# NeoGeo-JAMMA-Supergun_PP.net
KiCad netlist of a schematic drawn in EAGLE
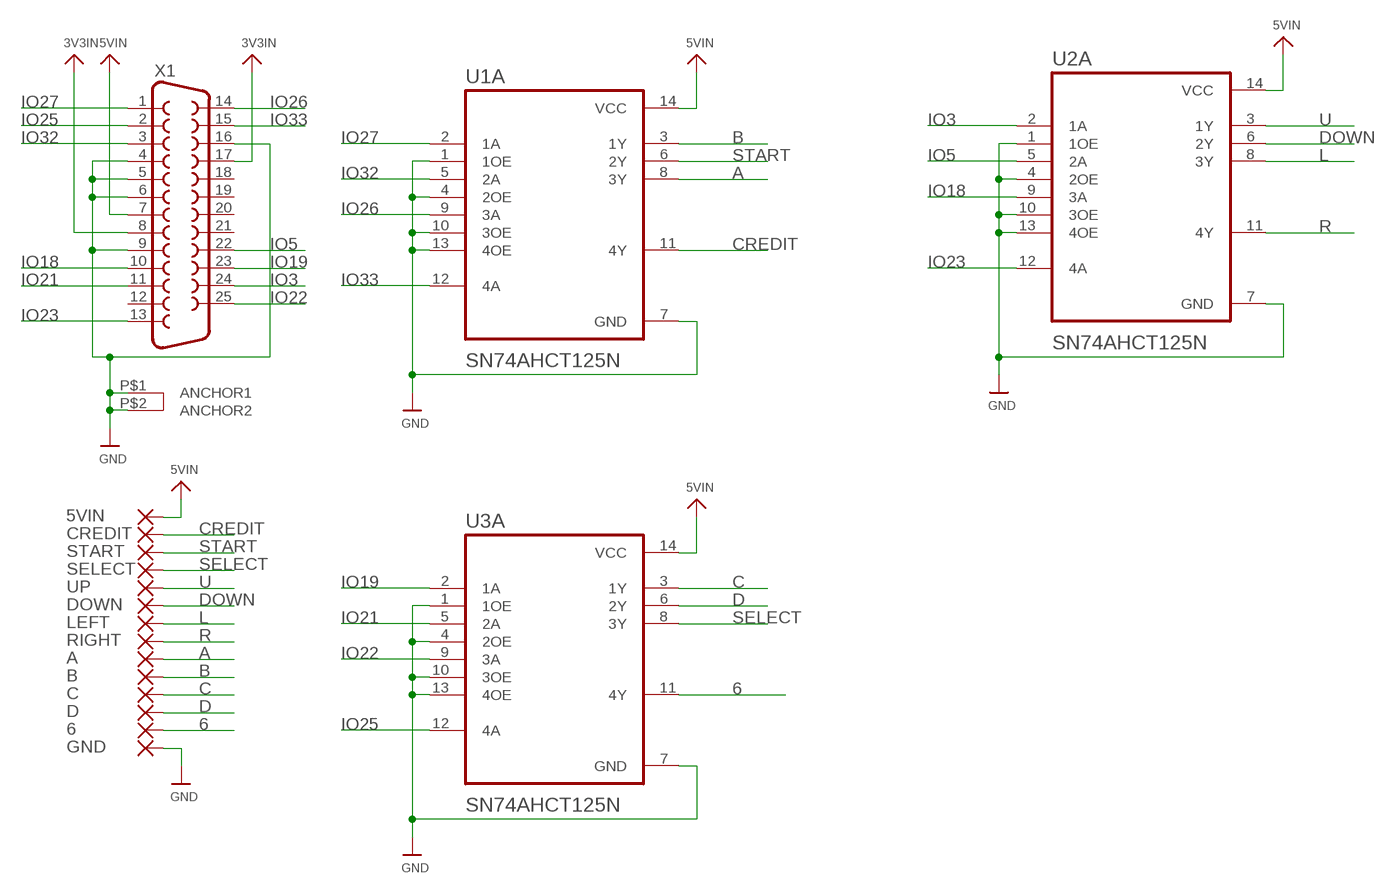
[diagram p0: schematic, sheet 1]

(export (version "E")
  (design (tool "Eeschema 10.0.6"))
  (components
    (comp (ref "5VIN")
      (value "SMD5")
      (footprint "eagle-import:SMD2,54-5,08")
      (libsource (lib "eagle-import") (part "SMD5"))
    )
    (comp (ref "6")
      (value "SMD5")
      (footprint "eagle-import:SMD2,54-5,08")
      (libsource (lib "eagle-import") (part "SMD5"))
    )
    (comp (ref "A")
      (value "SMD5")
      (footprint "eagle-import:SMD2,54-5,08")
      (libsource (lib "eagle-import") (part "SMD5"))
    )
    (comp (ref "B")
      (value "SMD5")
      (footprint "eagle-import:SMD2,54-5,08")
      (libsource (lib "eagle-import") (part "SMD5"))
    )
    (comp (ref "C")
      (value "SMD5")
      (footprint "eagle-import:SMD2,54-5,08")
      (libsource (lib "eagle-import") (part "SMD5"))
    )
    (comp (ref "CREDIT")
      (value "SMD5")
      (footprint "eagle-import:SMD2,54-5,08")
      (libsource (lib "eagle-import") (part "SMD5"))
    )
    (comp (ref "D")
      (value "SMD5")
      (footprint "eagle-import:SMD2,54-5,08")
      (libsource (lib "eagle-import") (part "SMD5"))
    )
    (comp (ref "DOWN")
      (value "SMD5")
      (footprint "eagle-import:SMD2,54-5,08")
      (libsource (lib "eagle-import") (part "SMD5"))
    )
    (comp (ref "GND")
      (value "SMD5")
      (footprint "eagle-import:SMD2,54-5,08")
      (libsource (lib "eagle-import") (part "SMD5"))
    )
    (comp (ref "LEFT")
      (value "SMD5")
      (footprint "eagle-import:SMD2,54-5,08")
      (libsource (lib "eagle-import") (part "SMD5"))
    )
    (comp (ref "RIGHT")
      (value "SMD5")
      (footprint "eagle-import:SMD2,54-5,08")
      (libsource (lib "eagle-import") (part "SMD5"))
    )
    (comp (ref "SELECT")
      (value "SMD5")
      (footprint "eagle-import:SMD2,54-5,08")
      (libsource (lib "eagle-import") (part "SMD5"))
    )
    (comp (ref "START")
      (value "SMD5")
      (footprint "eagle-import:SMD2,54-5,08")
      (libsource (lib "eagle-import") (part "SMD5"))
    )
    (comp (ref "U1A")
      (value "SN74AHCT125N")
      (footprint "eagle-import:DIP794W45P254L1969H508Q14")
      (fields (field (name "MF") "Texas Instruments"))
      (libsource (lib "eagle-import") (part "SN74AHCT125N"))
    )
    (comp (ref "U2A")
      (value "SN74AHCT125N")
      (footprint "eagle-import:DIP794W45P254L1969H508Q14")
      (fields (field (name "MF") "Texas Instruments"))
      (libsource (lib "eagle-import") (part "SN74AHCT125N"))
    )
    (comp (ref "U3A")
      (value "SN74AHCT125N")
      (footprint "eagle-import:DIP794W45P254L1969H508Q14")
      (fields (field (name "MF") "Texas Instruments"))
      (libsource (lib "eagle-import") (part "SN74AHCT125N"))
    )
    (comp (ref "UP")
      (value "SMD5")
      (footprint "eagle-import:SMD2,54-5,08")
      (libsource (lib "eagle-import") (part "SMD5"))
    )
    (comp (ref "X1")
      (value "DB25_FEMALEH")
      (footprint "eagle-import:F25H")
      (libsource (lib "eagle-import") (part "DB25_FEMALEH"))
    )
  )
  (nets
    (net (code "1") (name "/6") (class "Default")
      (node (ref "6") (pin "1") (pinfunction "P_1") (pintype "passive"))
      (node (ref "U3A") (pin "11") (pinfunction "4Y_11") (pintype "output"))
    )
    (net (code "2") (name "/A") (class "Default")
      (node (ref "A") (pin "1") (pinfunction "P_1") (pintype "passive"))
      (node (ref "U1A") (pin "8") (pinfunction "3Y_8") (pintype "output"))
    )
    (net (code "3") (name "/B") (class "Default")
      (node (ref "B") (pin "1") (pinfunction "P_1") (pintype "passive"))
      (node (ref "U1A") (pin "3") (pinfunction "1Y_3") (pintype "output"))
    )
    (net (code "4") (name "/C") (class "Default")
      (node (ref "C") (pin "1") (pinfunction "P_1") (pintype "passive"))
      (node (ref "U3A") (pin "3") (pinfunction "1Y_3") (pintype "output"))
    )
    (net (code "5") (name "/CREDIT") (class "Default")
      (node (ref "CREDIT") (pin "1") (pinfunction "P_1") (pintype "passive"))
      (node (ref "U1A") (pin "11") (pinfunction "4Y_11") (pintype "output"))
    )
    (net (code "6") (name "/D") (class "Default")
      (node (ref "D") (pin "1") (pinfunction "P_1") (pintype "passive"))
      (node (ref "U3A") (pin "6") (pinfunction "2Y_6") (pintype "output"))
    )
    (net (code "7") (name "/DOWN") (class "Default")
      (node (ref "DOWN") (pin "1") (pinfunction "P_1") (pintype "passive"))
      (node (ref "U2A") (pin "6") (pinfunction "2Y_6") (pintype "output"))
    )
    (net (code "8") (name "/IO3") (class "Default")
      (node (ref "U2A") (pin "2") (pinfunction "1A_2") (pintype "input"))
      (node (ref "X1") (pin "24") (pinfunction "24_24") (pintype "passive"))
    )
    (net (code "9") (name "/IO5") (class "Default")
      (node (ref "U2A") (pin "5") (pinfunction "2A_5") (pintype "input"))
      (node (ref "X1") (pin "22") (pinfunction "22_22") (pintype "passive"))
    )
    (net (code "10") (name "/IO18") (class "Default")
      (node (ref "U2A") (pin "9") (pinfunction "3A_9") (pintype "input"))
      (node (ref "X1") (pin "10") (pinfunction "10_10") (pintype "passive"))
    )
    (net (code "11") (name "/IO19") (class "Default")
      (node (ref "U3A") (pin "2") (pinfunction "1A_2") (pintype "input"))
      (node (ref "X1") (pin "23") (pinfunction "23_23") (pintype "passive"))
    )
    (net (code "12") (name "/IO21") (class "Default")
      (node (ref "U3A") (pin "5") (pinfunction "2A_5") (pintype "input"))
      (node (ref "X1") (pin "11") (pinfunction "11_11") (pintype "passive"))
    )
    (net (code "13") (name "/IO22") (class "Default")
      (node (ref "U3A") (pin "9") (pinfunction "3A_9") (pintype "input"))
      (node (ref "X1") (pin "25") (pinfunction "25_25") (pintype "passive"))
    )
    (net (code "14") (name "/IO23") (class "Default")
      (node (ref "U2A") (pin "12") (pinfunction "4A_12") (pintype "bidirectional"))
      (node (ref "X1") (pin "13") (pinfunction "13_13") (pintype "passive"))
    )
    (net (code "15") (name "/IO25") (class "Default")
      (node (ref "U3A") (pin "12") (pinfunction "4A_12") (pintype "bidirectional"))
      (node (ref "X1") (pin "2") (pinfunction "2_2") (pintype "passive"))
    )
    (net (code "16") (name "/IO26") (class "Default")
      (node (ref "U1A") (pin "9") (pinfunction "3A_9") (pintype "input"))
      (node (ref "X1") (pin "14") (pinfunction "14_14") (pintype "passive"))
    )
    (net (code "17") (name "/IO27") (class "Default")
      (node (ref "U1A") (pin "2") (pinfunction "1A_2") (pintype "input"))
      (node (ref "X1") (pin "1") (pinfunction "1_1") (pintype "passive"))
    )
    (net (code "18") (name "/IO32") (class "Default")
      (node (ref "U1A") (pin "5") (pinfunction "2A_5") (pintype "input"))
      (node (ref "X1") (pin "3") (pinfunction "3_3") (pintype "passive"))
    )
    (net (code "19") (name "/IO33") (class "Default")
      (node (ref "U1A") (pin "12") (pinfunction "4A_12") (pintype "bidirectional"))
      (node (ref "X1") (pin "15") (pinfunction "15_15") (pintype "passive"))
    )
    (net (code "20") (name "/L") (class "Default")
      (node (ref "LEFT") (pin "1") (pinfunction "P_1") (pintype "passive"))
      (node (ref "U2A") (pin "8") (pinfunction "3Y_8") (pintype "output"))
    )
    (net (code "21") (name "/R") (class "Default")
      (node (ref "RIGHT") (pin "1") (pinfunction "P_1") (pintype "passive"))
      (node (ref "U2A") (pin "11") (pinfunction "4Y_11") (pintype "output"))
    )
    (net (code "22") (name "/SELECT") (class "Default")
      (node (ref "SELECT") (pin "1") (pinfunction "P_1") (pintype "passive"))
      (node (ref "U3A") (pin "8") (pinfunction "3Y_8") (pintype "output"))
    )
    (net (code "23") (name "/START") (class "Default")
      (node (ref "START") (pin "1") (pinfunction "P_1") (pintype "passive"))
      (node (ref "U1A") (pin "6") (pinfunction "2Y_6") (pintype "output"))
    )
    (net (code "24") (name "/U") (class "Default")
      (node (ref "U2A") (pin "3") (pinfunction "1Y_3") (pintype "output"))
      (node (ref "UP") (pin "1") (pinfunction "P_1") (pintype "passive"))
    )
    (net (code "25") (name "3V3IN") (class "Default")
      (node (ref "X1") (pin "17") (pinfunction "17_17") (pintype "passive"))
      (node (ref "X1") (pin "8") (pinfunction "8_8") (pintype "passive"))
    )
    (net (code "26") (name "5VIN") (class "Default")
      (node (ref "5VIN") (pin "1") (pinfunction "P_1") (pintype "passive"))
      (node (ref "U1A") (pin "14") (pinfunction "VCC_14") (pintype "power_in"))
      (node (ref "U2A") (pin "14") (pinfunction "VCC_14") (pintype "power_in"))
      (node (ref "U3A") (pin "14") (pinfunction "VCC_14") (pintype "power_in"))
      (node (ref "X1") (pin "7") (pinfunction "7_7") (pintype "passive"))
    )
    (net (code "27") (name "GND") (class "Default")
      (node (ref "GND") (pin "1") (pinfunction "P_1") (pintype "passive"))
      (node (ref "U1A") (pin "1") (pinfunction "1OE_1") (pintype "input"))
      (node (ref "U1A") (pin "10") (pinfunction "3OE_10") (pintype "input"))
      (node (ref "U1A") (pin "13") (pinfunction "4OE_13") (pintype "input"))
      (node (ref "U1A") (pin "4") (pinfunction "2OE_4") (pintype "input"))
      (node (ref "U1A") (pin "7") (pinfunction "GND_7") (pintype "power_in"))
      (node (ref "U2A") (pin "1") (pinfunction "1OE_1") (pintype "input"))
      (node (ref "U2A") (pin "10") (pinfunction "3OE_10") (pintype "input"))
      (node (ref "U2A") (pin "13") (pinfunction "4OE_13") (pintype "input"))
      (node (ref "U2A") (pin "4") (pinfunction "2OE_4") (pintype "input"))
      (node (ref "U2A") (pin "7") (pinfunction "GND_7") (pintype "power_in"))
      (node (ref "U3A") (pin "1") (pinfunction "1OE_1") (pintype "input"))
      (node (ref "U3A") (pin "10") (pinfunction "3OE_10") (pintype "input"))
      (node (ref "U3A") (pin "13") (pinfunction "4OE_13") (pintype "input"))
      (node (ref "U3A") (pin "4") (pinfunction "2OE_4") (pintype "input"))
      (node (ref "U3A") (pin "7") (pinfunction "GND_7") (pintype "power_in"))
      (node (ref "X1") (pin "16") (pinfunction "16_16") (pintype "passive"))
      (node (ref "X1") (pin "4") (pinfunction "4_4") (pintype "passive"))
      (node (ref "X1") (pin "5") (pinfunction "5_5") (pintype "passive"))
      (node (ref "X1") (pin "6") (pinfunction "6_6") (pintype "passive"))
      (node (ref "X1") (pin "9") (pinfunction "9_9") (pintype "passive"))
      (node (ref "X1") (pin "P$1") (pinfunction "ANCHOR1_P$1") (pintype "bidirectional"))
      (node (ref "X1") (pin "P$2") (pinfunction "ANCHOR2_P$2") (pintype "bidirectional"))
    )
    (net (code "28") (name "unconnected-(X1-Pad12)") (class "Default")
      (node (ref "X1") (pin "12") (pinfunction "12_12") (pintype "passive"))
    )
    (net (code "29") (name "unconnected-(X1-Pad18)") (class "Default")
      (node (ref "X1") (pin "18") (pinfunction "18_18") (pintype "passive"))
    )
    (net (code "30") (name "unconnected-(X1-Pad19)") (class "Default")
      (node (ref "X1") (pin "19") (pinfunction "19_19") (pintype "passive"))
    )
    (net (code "31") (name "unconnected-(X1-Pad20)") (class "Default")
      (node (ref "X1") (pin "20") (pinfunction "20_20") (pintype "passive"))
    )
    (net (code "32") (name "unconnected-(X1-Pad21)") (class "Default")
      (node (ref "X1") (pin "21") (pinfunction "21_21") (pintype "passive"))
    )
  )
)
